# protect2.net
KiCad netlist of a schematic drawn in Altium Designer
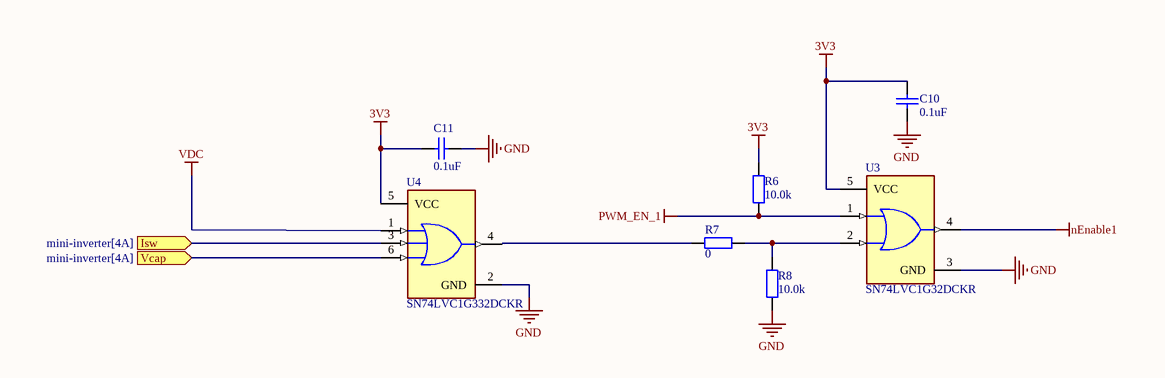
[diagram p0: protect2.SchDoc]

(export (version "E")
  (design (tool "Eeschema 10.0.6"))
  (components
    (comp (ref "C10")
      (value "0.1uF")
      (footprint "CAPC1608X06N")
      (description "Capacitor")
      (fields (field (name "PUBLISHER") "Altium Limited"))
      (libsource (lib "Simscale") (part "Cap"))
    )
    (comp (ref "C11")
      (value "0.1uF")
      (footprint "CAPC1608X06N")
      (description "Capacitor")
      (fields (field (name "PUBLISHER") "Altium Limited"))
      (libsource (lib "Simscale") (part "Cap"))
    )
    (comp (ref "R6")
      (value "10.0k")
      (footprint "RESC1608X05N")
      (description "贴片电阻")
      (libsource (lib "Simscale") (part "0603 100KΩ (1003) 1%_4"))
    )
    (comp (ref "R7")
      (value "0")
      (footprint "RESC1608X05N")
      (description "贴片电阻")
      (libsource (lib "") (part "0603 100KΩ (1003) 1%_4_2"))
    )
    (comp (ref "R8")
      (value "10.0k")
      (footprint "RESC1608X05N")
      (description "贴片电阻")
      (libsource (lib "") (part "0603 100KΩ (1003) 1%_4_1"))
    )
    (comp (ref "U3")
      (value "SN74LVC1G32DCKR")
      (footprint "FP-DCK0005A-IPC_A")
      (description "IC GATE OR 1CH 2-INP SC70-5")
      (libsource (lib "Altium Content Vault") (part "9a4003fa4a62225b3c2fa1ca1eebe37"))
    )
    (comp (ref "U4")
      (value "SN74LVC1G332DCKR")
      (footprint "FP-DCK0006A-MFG")
      (description "IC GATE OR 1CH 3-INP SC70-6")
      (fields
        (field (name "MANUFACTURER") "Texas Instruments")
        (field (name "OCTOPART") "https://octopart.com/sn74lvc1g332dckr-texas+instruments-464861")
      )
      (libsource (lib "Altium Content Vault") (part "a1fbee6839145229a27344b52c53a8d"))
    )
  )
  (nets
    (net (code "1") (name "/Isw") (class "Default")
      (node (ref "U4") (pin "3") (pinfunction "B_3") (pintype "input"))
    )
    (net (code "2") (name "/Vcap") (class "Default")
      (node (ref "U4") (pin "6") (pinfunction "C_6") (pintype "input"))
    )
    (net (code "3") (name "3V3") (class "Default")
      (node (ref "C10") (pin "1") (pinfunction "1_1") (pintype "passive"))
      (node (ref "C11") (pin "1") (pinfunction "1_1") (pintype "passive"))
      (node (ref "R6") (pin "1") (pinfunction "1_1") (pintype "passive"))
      (node (ref "U3") (pin "5") (pinfunction "VCC_5") (pintype "power_in"))
    )
    (net (code "4") (name "GND") (class "Default")
      (node (ref "C10") (pin "2") (pinfunction "2_2") (pintype "passive"))
      (node (ref "C11") (pin "2") (pinfunction "2_2") (pintype "passive"))
      (node (ref "R8") (pin "1") (pinfunction "1_1") (pintype "passive"))
      (node (ref "U3") (pin "3") (pinfunction "GND_3") (pintype "power_in"))
      (node (ref "U4") (pin "2") (pinfunction "GND_2") (pintype "power_in"))
    )
    (net (code "5") (name "Net-(U3-B)") (class "Default")
      (node (ref "R7") (pin "2") (pinfunction "2_2") (pintype "passive"))
      (node (ref "R8") (pin "2") (pinfunction "2_2") (pintype "passive"))
      (node (ref "U3") (pin "2") (pinfunction "B_2") (pintype "input"))
    )
    (net (code "6") (name "PWM_EN_1") (class "Default")
      (node (ref "R6") (pin "2") (pinfunction "2_2") (pintype "passive"))
      (node (ref "U3") (pin "1") (pinfunction "A_1") (pintype "input"))
    )
    (net (code "7") (name "VDC") (class "Default")
      (node (ref "U4") (pin "1") (pinfunction "A_1") (pintype "input"))
    )
    (net (code "8") (name "nEnable1") (class "Default")
      (node (ref "U3") (pin "4") (pinfunction "Y_4") (pintype "output"))
    )
    (net (code "9") (name "unconnected-(R7-Pad1)") (class "Default")
      (node (ref "R7") (pin "1") (pinfunction "1_1") (pintype "passive"))
    )
    (net (code "10") (name "unconnected-(U4-VCC-Pad5)") (class "Default")
      (node (ref "U4") (pin "5") (pinfunction "VCC_5") (pintype "power_in"))
    )
    (net (code "11") (name "unconnected-(U4-Y-Pad4)") (class "Default")
      (node (ref "U4") (pin "4") (pinfunction "Y_4") (pintype "output"))
    )
  )
)
